# modFOC-Inputs.net
KiCad netlist of a schematic drawn in Altium Designer
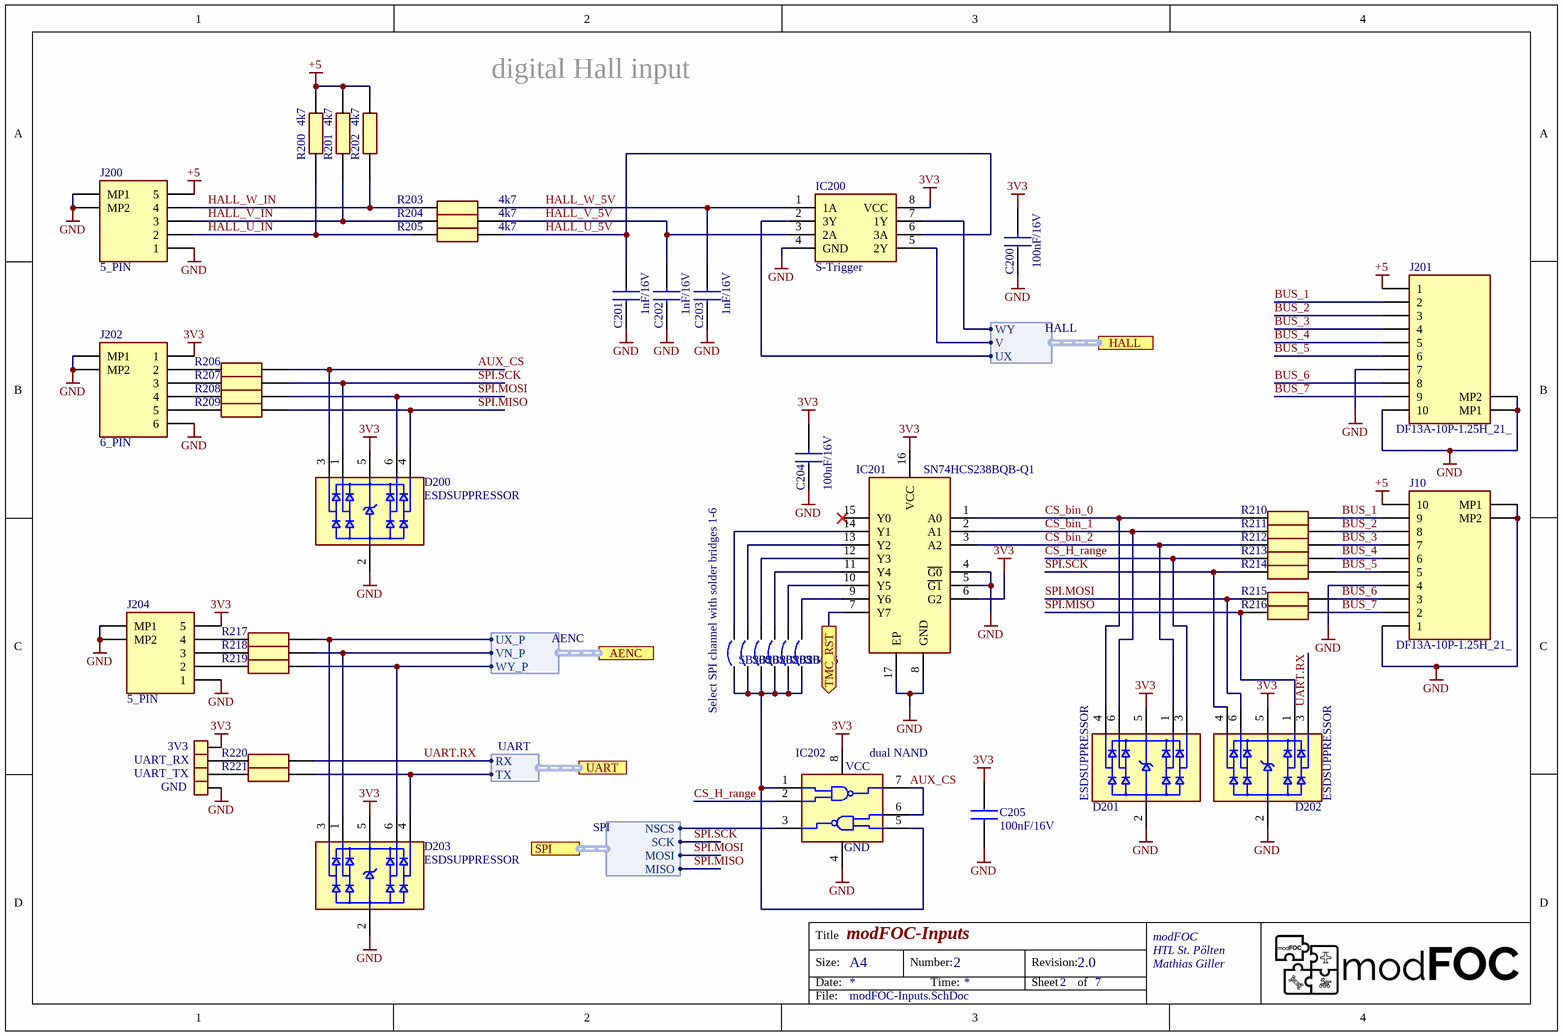
[diagram p0: modFOC-Inputs.SchDoc]

(export (version "E")
  (design (tool "Eeschema 10.0.6"))
  (components
    (comp (ref "C200")
      (value "100nF/16V")
      (footprint "CAPC1608X97N")
      (description "Capacitor")
      (libsource (lib "Schlib1") (part "C0603"))
    )
    (comp (ref "C201")
      (value "1nF/16V")
      (footprint "CAPC1608X97N")
      (description "Capacitor")
      (libsource (lib "Schlib1") (part "C0603"))
    )
    (comp (ref "C202")
      (value "1nF/16V")
      (footprint "CAPC1608X97N")
      (description "Capacitor")
      (libsource (lib "Schlib1") (part "C0603"))
    )
    (comp (ref "C203")
      (value "1nF/16V")
      (footprint "CAPC1608X97N")
      (description "Capacitor")
      (libsource (lib "Schlib1") (part "C0603"))
    )
    (comp (ref "C204")
      (value "100nF/16V")
      (footprint "CAPC1608X97N")
      (description "Capacitor")
      (libsource (lib "Schlib1") (part "C0603"))
    )
    (comp (ref "C205")
      (value "100nF/16V")
      (footprint "CAPC1608X97N")
      (description "Capacitor")
      (libsource (lib "Schlib1") (part "C0603"))
    )
    (comp (ref "D200")
      (value "ESDSUPPRESSOR")
      (footprint "SOT23-6")
      (description "TVS Diode (Uni-directional)")
      (libsource (lib "Schlib1") (part "ESDSUPPRESSOR"))
    )
    (comp (ref "D201")
      (value "ESDSUPPRESSOR")
      (footprint "SOT23-6")
      (description "TVS Diode (Uni-directional)")
      (libsource (lib "Schlib1") (part "ESDSUPPRESSOR"))
    )
    (comp (ref "D202")
      (value "ESDSUPPRESSOR")
      (footprint "SOT23-6")
      (description "TVS Diode (Uni-directional)")
      (libsource (lib "Schlib1") (part "ESDSUPPRESSOR"))
    )
    (comp (ref "D203")
      (value "ESDSUPPRESSOR")
      (footprint "SOT23-6")
      (description "TVS Diode (Uni-directional)")
      (libsource (lib "Schlib1") (part "ESDSUPPRESSOR"))
    )
    (comp (ref "IC200")
      (value "S-Trigger")
      (footprint "SOP65P400X110-8N")
      (description "3x Schmitt trigger")
      (fields
        (field (name "MANUFACTURER_PART_NUMBER") "74LVC3G17DP,125")
        (field (name "MOUSER PART NUMBER") "771-LVC3G17DP125")
      )
      (libsource (lib "Schlib1") (part "74LVC3G17DP,125"))
    )
    (comp (ref "IC201")
      (value "SN74HCS238BQB-Q1")
      (footprint "SN74HCS238BQB-Q1")
      (description "3bit bin to dec noninverting")
      (fields
        (field (name "MANUFACTURER_PART_NUMBER") "SN74HCS238QBQBRQ1")
        (field (name "MOUSER PART NUMBER") "595-N74HCS238QBQBRQ1")
      )
      (libsource (lib "Schlib1") (part "SN74HCS238BQB-Q1"))
    )
    (comp (ref "IC202")
      (value "dual NAND")
      (footprint "74AUP1G74GF115")
      (description "Dual triple input NAND")
      (fields
        (field (name "MANUFACTURER_PART_NUMBER") "74AUP2G132GF,115")
        (field (name "MOUSER PART NUMBER") "771-74AUP2G132GF115")
      )
      (libsource (lib "Schlib1") (part "74AUP2G132GF,115"))
    )
    (comp (ref "J10")
      (value "DF13A-10P-1.25H_21_")
      (footprint "DF13A10P125H21")
      (description "10Pin DF13 Connector")
      (fields
        (field (name "MANUFACTURER_PART_NUMBER") "DF13A-10P-1.25H(21)")
        (field (name "MOUSER PART NUMBER") "798-DF13A10P125H21")
      )
      (libsource (lib "") (part "DF13A-10P-1.25H_21__1"))
    )
    (comp (ref "J200")
      (value "5_PIN")
      (footprint "DF13A5P125H21")
      (description "Connector")
      (fields
        (field (name "MANUFACTURER_PART_NUMBER") "DF13A-5P-1.25H(21)")
        (field (name "MOUSER PART NUMBER") "798-DF13A5P125H21")
      )
      (libsource (lib "Schlib1") (part "DF13A-5P-1.25H_21_"))
    )
    (comp (ref "J201")
      (value "DF13A-10P-1.25H_21_")
      (footprint "DF13A10P125H21")
      (description "10Pin DF13 Connector")
      (fields
        (field (name "MANUFACTURER_PART_NUMBER") "DF13A-10P-1.25H(21)")
        (field (name "MOUSER PART NUMBER") "798-DF13A10P125H21")
      )
      (libsource (lib "Schlib1") (part "DF13A-10P-1.25H_21_"))
    )
    (comp (ref "J202")
      (value "6_PIN")
      (footprint "DF13A6P125H21")
      (description "6 Pin DF13 Connector")
      (fields
        (field (name "MANUFACTURER_PART_NUMBER") "DF13A-6P-1.25H(21)")
        (field (name "MOUSER PART NUMBER") "798-DF13A6P125H21")
      )
      (libsource (lib "Schlib1") (part "DF13A-6P-1.25H_21_"))
    )
    (comp (ref "J204")
      (value "5_PIN")
      (footprint "DF13A5P125H21")
      (description "Connector")
      (fields
        (field (name "MANUFACTURER_PART_NUMBER") "DF13A-5P-1.25H(21)")
        (field (name "MOUSER PART NUMBER") "798-DF13A5P125H21")
      )
      (libsource (lib "Schlib1") (part "DF13A-5P-1.25H_21_"))
    )
    (comp (ref "J205") (value "3V3") (footprint "Pin") (libsource (lib "Schlib1") (part "Pin")))
    (comp (ref "J206") (value "UART_RX") (footprint "Pin") (libsource (lib "Schlib1") (part "Pin")))
    (comp (ref "J207") (value "UART_TX") (footprint "Pin") (libsource (lib "Schlib1") (part "Pin")))
    (comp (ref "J208") (value "GND") (footprint "Pin") (libsource (lib "Schlib1") (part "Pin")))
    (comp (ref "R200")
      (value "4k7")
      (footprint "RESC1608X55N")
      (description "Resistor")
      (libsource (lib "Schlib1") (part "R0603"))
    )
    (comp (ref "R201")
      (value "4k7")
      (footprint "RESC1608X55N")
      (description "Resistor")
      (libsource (lib "Schlib1") (part "R0603"))
    )
    (comp (ref "R202")
      (value "4k7")
      (footprint "RESC1608X55N")
      (description "Resistor")
      (libsource (lib "Schlib1") (part "R0603"))
    )
    (comp (ref "R203")
      (value "4k7")
      (footprint "RESC1608X55N")
      (description "Resistor")
      (libsource (lib "") (part "R0603_1"))
    )
    (comp (ref "R204")
      (value "4k7")
      (footprint "RESC1608X55N")
      (description "Resistor")
      (libsource (lib "") (part "R0603_1"))
    )
    (comp (ref "R205")
      (value "4k7")
      (footprint "RESC1608X55N")
      (description "Resistor")
      (libsource (lib "") (part "R0603_1"))
    )
    (comp (ref "R206")
      (value "100R")
      (footprint "RESC1005X40N")
      (description "Resistor")
      (libsource (lib "Schlib1") (part "R0402"))
    )
    (comp (ref "R207")
      (value "100R")
      (footprint "RESC1005X40N")
      (description "Resistor")
      (libsource (lib "Schlib1") (part "R0402"))
    )
    (comp (ref "R208")
      (value "100R")
      (footprint "RESC1005X40N")
      (description "Resistor")
      (libsource (lib "Schlib1") (part "R0402"))
    )
    (comp (ref "R209")
      (value "100R")
      (footprint "RESC1005X40N")
      (description "Resistor")
      (libsource (lib "Schlib1") (part "R0402"))
    )
    (comp (ref "R210")
      (value "100R")
      (footprint "RESC1005X40N")
      (description "Resistor")
      (libsource (lib "Schlib1") (part "R0402"))
    )
    (comp (ref "R211")
      (value "100R")
      (footprint "RESC1005X40N")
      (description "Resistor")
      (libsource (lib "Schlib1") (part "R0402"))
    )
    (comp (ref "R212")
      (value "100R")
      (footprint "RESC1005X40N")
      (description "Resistor")
      (libsource (lib "Schlib1") (part "R0402"))
    )
    (comp (ref "R213")
      (value "100R")
      (footprint "RESC1005X40N")
      (description "Resistor")
      (libsource (lib "Schlib1") (part "R0402"))
    )
    (comp (ref "R214")
      (value "100R")
      (footprint "RESC1005X40N")
      (description "Resistor")
      (libsource (lib "Schlib1") (part "R0402"))
    )
    (comp (ref "R215")
      (value "100R")
      (footprint "RESC1005X40N")
      (description "Resistor")
      (libsource (lib "Schlib1") (part "R0402"))
    )
    (comp (ref "R216")
      (value "100R")
      (footprint "RESC1005X40N")
      (description "Resistor")
      (libsource (lib "Schlib1") (part "R0402"))
    )
    (comp (ref "R217")
      (value "100R")
      (footprint "RESC1005X40N")
      (description "Resistor")
      (libsource (lib "Schlib1") (part "R0402"))
    )
    (comp (ref "R218")
      (value "100R")
      (footprint "RESC1005X40N")
      (description "Resistor")
      (libsource (lib "Schlib1") (part "R0402"))
    )
    (comp (ref "R219")
      (value "100R")
      (footprint "RESC1005X40N")
      (description "Resistor")
      (libsource (lib "Schlib1") (part "R0402"))
    )
    (comp (ref "R220")
      (value "100R")
      (footprint "RESC1005X40N")
      (description "Resistor")
      (libsource (lib "Schlib1") (part "R0402"))
    )
    (comp (ref "R221")
      (value "100R")
      (footprint "RESC1005X40N")
      (description "Resistor")
      (libsource (lib "Schlib1") (part "R0402"))
    )
    (comp (ref "SB200")
      (value "Solder Bridge")
      (footprint "PcbLib1:SOLDER-BRIDGE_R0603-0R")
      (fields
        (field (name "INTERNAL_PART_NUMBER") "MCD-00071")
        (field (name "MANUFACTURER_PART_NUMBER") "RC0603JR-070RL")
        (field (name "MANUFACTURER") "YAGEO")
        (field (name "PROVIDED_BY") "SUBCO")
      )
      (libsource (lib "Schlib1") (part "Solder Bridge"))
    )
    (comp (ref "SB201")
      (value "Solder Bridge")
      (footprint "PcbLib1:SOLDER-BRIDGE_R0603-0R")
      (fields
        (field (name "INTERNAL_PART_NUMBER") "MCD-00071")
        (field (name "MANUFACTURER_PART_NUMBER") "RC0603JR-070RL")
        (field (name "MANUFACTURER") "YAGEO")
        (field (name "PROVIDED_BY") "SUBCO")
      )
      (libsource (lib "Schlib1") (part "Solder Bridge"))
    )
    (comp (ref "SB202")
      (value "Solder Bridge")
      (footprint "PcbLib1:SOLDER-BRIDGE_R0603-0R")
      (fields
        (field (name "INTERNAL_PART_NUMBER") "MCD-00071")
        (field (name "MANUFACTURER_PART_NUMBER") "RC0603JR-070RL")
        (field (name "MANUFACTURER") "YAGEO")
        (field (name "PROVIDED_BY") "SUBCO")
      )
      (libsource (lib "Schlib1") (part "Solder Bridge"))
    )
    (comp (ref "SB203")
      (value "Solder Bridge")
      (footprint "PcbLib1:SOLDER-BRIDGE_R0603-0R")
      (fields
        (field (name "INTERNAL_PART_NUMBER") "MCD-00071")
        (field (name "MANUFACTURER_PART_NUMBER") "RC0603JR-070RL")
        (field (name "MANUFACTURER") "YAGEO")
        (field (name "PROVIDED_BY") "SUBCO")
      )
      (libsource (lib "Schlib1") (part "Solder Bridge"))
    )
    (comp (ref "SB204")
      (value "Solder Bridge")
      (footprint "PcbLib1:SOLDER-BRIDGE_R0603-0R")
      (fields
        (field (name "INTERNAL_PART_NUMBER") "MCD-00071")
        (field (name "MANUFACTURER_PART_NUMBER") "RC0603JR-070RL")
        (field (name "MANUFACTURER") "YAGEO")
        (field (name "PROVIDED_BY") "SUBCO")
      )
      (libsource (lib "Schlib1") (part "Solder Bridge"))
    )
    (comp (ref "SB205")
      (value "Solder Bridge")
      (footprint "PcbLib1:SOLDER-BRIDGE_R0603-0R")
      (fields
        (field (name "INTERNAL_PART_NUMBER") "MCD-00071")
        (field (name "MANUFACTURER_PART_NUMBER") "RC0603JR-070RL")
        (field (name "MANUFACTURER") "YAGEO")
        (field (name "PROVIDED_BY") "SUBCO")
      )
      (libsource (lib "Schlib1") (part "Solder Bridge"))
    )
  )
  (nets
    (net (code "5") (name "+5") (class "Default")
      (node (ref "J10") (pin "10") (pinfunction "10_10") (pintype "passive"))
      (node (ref "J200") (pin "5") (pinfunction "5_5") (pintype "passive"))
      (node (ref "J201") (pin "1") (pinfunction "1_1") (pintype "passive"))
      (node (ref "R200") (pin "2") (pinfunction "2_2") (pintype "passive"))
      (node (ref "R201") (pin "2") (pinfunction "2_2") (pintype "passive"))
      (node (ref "R202") (pin "2") (pinfunction "2_2") (pintype "passive"))
    )
    (net (code "6") (name "/AUX_CS") (class "Default")
      (node (ref "D200") (pin "3") (pinfunction "CH1_3") (pintype "passive"))
      (node (ref "IC202") (pin "6") (pinfunction "2B_6") (pintype "passive"))
      (node (ref "IC202") (pin "7") (pinfunction "1Y_7") (pintype "passive"))
      (node (ref "R206") (pin "2") (pinfunction "2_2") (pintype "passive"))
    )
    (net (code "7") (name "/BUS_1") (class "Default")
      (node (ref "J10") (pin "9") (pinfunction "9_9") (pintype "passive"))
      (node (ref "J201") (pin "2") (pinfunction "2_2") (pintype "passive"))
      (node (ref "R210") (pin "2") (pinfunction "2_2") (pintype "passive"))
    )
    (net (code "8") (name "/BUS_2") (class "Default")
      (node (ref "J10") (pin "8") (pinfunction "8_8") (pintype "passive"))
      (node (ref "J201") (pin "3") (pinfunction "3_3") (pintype "passive"))
      (node (ref "R211") (pin "2") (pinfunction "2_2") (pintype "passive"))
    )
    (net (code "9") (name "/BUS_3") (class "Default")
      (node (ref "J10") (pin "7") (pinfunction "7_7") (pintype "passive"))
      (node (ref "J201") (pin "4") (pinfunction "4_4") (pintype "passive"))
      (node (ref "R212") (pin "2") (pinfunction "2_2") (pintype "passive"))
    )
    (net (code "10") (name "/BUS_4") (class "Default")
      (node (ref "J10") (pin "6") (pinfunction "6_6") (pintype "passive"))
      (node (ref "J201") (pin "5") (pinfunction "5_5") (pintype "passive"))
      (node (ref "R213") (pin "2") (pinfunction "2_2") (pintype "passive"))
    )
    (net (code "11") (name "/BUS_5") (class "Default")
      (node (ref "J10") (pin "5") (pinfunction "5_5") (pintype "passive"))
      (node (ref "J201") (pin "6") (pinfunction "6_6") (pintype "passive"))
      (node (ref "R214") (pin "2") (pinfunction "2_2") (pintype "passive"))
    )
    (net (code "12") (name "/BUS_6") (class "Default")
      (node (ref "J10") (pin "3") (pinfunction "3_3") (pintype "passive"))
      (node (ref "J201") (pin "8") (pinfunction "8_8") (pintype "passive"))
      (node (ref "R215") (pin "2") (pinfunction "2_2") (pintype "passive"))
    )
    (net (code "13") (name "/BUS_7") (class "Default")
      (node (ref "J10") (pin "2") (pinfunction "2_2") (pintype "passive"))
      (node (ref "J201") (pin "9") (pinfunction "9_9") (pintype "passive"))
      (node (ref "R216") (pin "2") (pinfunction "2_2") (pintype "passive"))
    )
    (net (code "14") (name "/CS_H_range") (class "Default")
      (node (ref "D201") (pin "3") (pinfunction "CH1_3") (pintype "passive"))
      (node (ref "IC202") (pin "2") (pinfunction "1B_2") (pintype "passive"))
      (node (ref "R213") (pin "1") (pinfunction "1_1") (pintype "passive"))
    )
    (net (code "15") (name "/CS_bin_0") (class "Default")
      (node (ref "D201") (pin "4") (pinfunction "CH3_4") (pintype "passive"))
      (node (ref "IC201") (pin "1") (pinfunction "A0_1") (pintype "passive"))
      (node (ref "R210") (pin "1") (pinfunction "1_1") (pintype "passive"))
    )
    (net (code "16") (name "/CS_bin_1") (class "Default")
      (node (ref "D201") (pin "6") (pinfunction "CH2_6") (pintype "passive"))
      (node (ref "IC201") (pin "2") (pinfunction "A1_2") (pintype "passive"))
      (node (ref "R211") (pin "1") (pinfunction "1_1") (pintype "passive"))
    )
    (net (code "17") (name "/CS_bin_2") (class "Default")
      (node (ref "D201") (pin "1") (pinfunction "CH4_1") (pintype "passive"))
      (node (ref "IC201") (pin "3") (pinfunction "A2_3") (pintype "passive"))
      (node (ref "R212") (pin "1") (pinfunction "1_1") (pintype "passive"))
    )
    (net (code "18") (name "/HALL_U_5V") (class "Default")
      (node (ref "C201") (pin "1") (pinfunction "1_1") (pintype "passive"))
      (node (ref "IC200") (pin "6") (pinfunction "3A_6") (pintype "passive"))
      (node (ref "R205") (pin "1") (pinfunction "1_1") (pintype "passive"))
    )
    (net (code "19") (name "/HALL_U_IN") (class "Default")
      (node (ref "J200") (pin "2") (pinfunction "2_2") (pintype "passive"))
      (node (ref "R200") (pin "1") (pinfunction "1_1") (pintype "passive"))
      (node (ref "R205") (pin "2") (pinfunction "2_2") (pintype "passive"))
    )
    (net (code "20") (name "/HALL_V_5V") (class "Default")
      (node (ref "C202") (pin "1") (pinfunction "1_1") (pintype "passive"))
      (node (ref "IC200") (pin "3") (pinfunction "2A_3") (pintype "passive"))
      (node (ref "R204") (pin "1") (pinfunction "1_1") (pintype "passive"))
    )
    (net (code "21") (name "/HALL_V_IN") (class "Default")
      (node (ref "J200") (pin "3") (pinfunction "3_3") (pintype "passive"))
      (node (ref "R201") (pin "1") (pinfunction "1_1") (pintype "passive"))
      (node (ref "R204") (pin "2") (pinfunction "2_2") (pintype "passive"))
    )
    (net (code "22") (name "/HALL_W_5V") (class "Default")
      (node (ref "C203") (pin "1") (pinfunction "1_1") (pintype "passive"))
      (node (ref "IC200") (pin "1") (pinfunction "1A_1") (pintype "passive"))
      (node (ref "R203") (pin "1") (pinfunction "1_1") (pintype "passive"))
    )
    (net (code "23") (name "/HALL_W_IN") (class "Default")
      (node (ref "J200") (pin "4") (pinfunction "4_4") (pintype "passive"))
      (node (ref "R202") (pin "1") (pinfunction "1_1") (pintype "passive"))
      (node (ref "R203") (pin "2") (pinfunction "2_2") (pintype "passive"))
    )
    (net (code "24") (name "/NSCS") (class "Default")
      (node (ref "IC202") (pin "3") (pinfunction "2Y_3") (pintype "passive"))
    )
    (net (code "25") (name "/SPI.MISO") (class "Default")
      (node (ref "D200") (pin "4") (pinfunction "CH3_4") (pintype "passive"))
      (node (ref "D202") (pin "1") (pinfunction "CH4_1") (pintype "passive"))
      (node (ref "R209") (pin "2") (pinfunction "2_2") (pintype "passive"))
      (node (ref "R216") (pin "1") (pinfunction "1_1") (pintype "passive"))
    )
    (net (code "26") (name "/SPI.MOSI") (class "Default")
      (node (ref "D200") (pin "6") (pinfunction "CH2_6") (pintype "passive"))
      (node (ref "D202") (pin "6") (pinfunction "CH2_6") (pintype "passive"))
      (node (ref "R208") (pin "2") (pinfunction "2_2") (pintype "passive"))
      (node (ref "R215") (pin "1") (pinfunction "1_1") (pintype "passive"))
    )
    (net (code "27") (name "/SPI.SCK") (class "Default")
      (node (ref "D200") (pin "1") (pinfunction "CH4_1") (pintype "passive"))
      (node (ref "D202") (pin "4") (pinfunction "CH3_4") (pintype "passive"))
      (node (ref "R207") (pin "2") (pinfunction "2_2") (pintype "passive"))
      (node (ref "R214") (pin "1") (pinfunction "1_1") (pintype "passive"))
    )
    (net (code "28") (name "/TMC_RST") (class "Default")
      (node (ref "IC201") (pin "7") (pinfunction "Y7_7") (pintype "passive"))
    )
    (net (code "29") (name "/TX") (class "Default")
      (node (ref "D203") (pin "4") (pinfunction "CH3_4") (pintype "passive"))
      (node (ref "R221") (pin "2") (pinfunction "2_2") (pintype "passive"))
    )
    (net (code "30") (name "/UART.RX") (class "Default")
      (node (ref "D202") (pin "3") (pinfunction "CH1_3") (pintype "passive"))
      (node (ref "R220") (pin "2") (pinfunction "2_2") (pintype "passive"))
    )
    (net (code "31") (name "/UX") (class "Default")
      (node (ref "IC200") (pin "2") (pinfunction "3Y_2") (pintype "passive"))
    )
    (net (code "32") (name "/UX_P") (class "Default")
      (node (ref "D203") (pin "3") (pinfunction "CH1_3") (pintype "passive"))
      (node (ref "R217") (pin "2") (pinfunction "2_2") (pintype "passive"))
    )
    (net (code "33") (name "/V") (class "Default")
      (node (ref "IC200") (pin "5") (pinfunction "2Y_5") (pintype "passive"))
    )
    (net (code "34") (name "/VN_P") (class "Default")
      (node (ref "D203") (pin "1") (pinfunction "CH4_1") (pintype "passive"))
      (node (ref "R218") (pin "2") (pinfunction "2_2") (pintype "passive"))
    )
    (net (code "35") (name "/WY") (class "Default")
      (node (ref "IC200") (pin "7") (pinfunction "1Y_7") (pintype "passive"))
    )
    (net (code "36") (name "/WY_P") (class "Default")
      (node (ref "D203") (pin "6") (pinfunction "CH2_6") (pintype "passive"))
      (node (ref "R219") (pin "2") (pinfunction "2_2") (pintype "passive"))
    )
    (net (code "41") (name "3V3") (class "Default")
      (node (ref "C200") (pin "2") (pinfunction "2_2") (pintype "passive"))
      (node (ref "C204") (pin "1") (pinfunction "1_1") (pintype "passive"))
      (node (ref "C205") (pin "1") (pinfunction "1_1") (pintype "passive"))
      (node (ref "D200") (pin "5") (pinfunction "VDD_5") (pintype "passive"))
      (node (ref "D201") (pin "5") (pinfunction "VDD_5") (pintype "passive"))
      (node (ref "D202") (pin "5") (pinfunction "VDD_5") (pintype "passive"))
      (node (ref "D203") (pin "5") (pinfunction "VDD_5") (pintype "passive"))
      (node (ref "IC200") (pin "8") (pinfunction "VCC_8") (pintype "passive"))
      (node (ref "IC201") (pin "16") (pinfunction "VCC_16") (pintype "passive"))
      (node (ref "IC201") (pin "6") (pinfunction "G2_6") (pintype "passive"))
      (node (ref "IC202") (pin "8") (pintype "passive"))
      (node (ref "J202") (pin "1") (pinfunction "1_1") (pintype "passive"))
      (node (ref "J204") (pin "5") (pinfunction "5_5") (pintype "passive"))
      (node (ref "J205") (pin "1") (pinfunction "1_1") (pintype "passive"))
    )
    (net (code "42") (name "GND") (class "Default")
      (node (ref "C200") (pin "1") (pinfunction "1_1") (pintype "passive"))
      (node (ref "C201") (pin "2") (pinfunction "2_2") (pintype "passive"))
      (node (ref "C202") (pin "2") (pinfunction "2_2") (pintype "passive"))
      (node (ref "C203") (pin "2") (pinfunction "2_2") (pintype "passive"))
      (node (ref "C204") (pin "2") (pinfunction "2_2") (pintype "passive"))
      (node (ref "C205") (pin "2") (pinfunction "2_2") (pintype "passive"))
      (node (ref "D200") (pin "2") (pinfunction "GND_2") (pintype "passive"))
      (node (ref "D201") (pin "2") (pinfunction "GND_2") (pintype "passive"))
      (node (ref "D202") (pin "2") (pinfunction "GND_2") (pintype "passive"))
      (node (ref "D203") (pin "2") (pinfunction "GND_2") (pintype "passive"))
      (node (ref "IC200") (pin "4") (pinfunction "GND_4") (pintype "passive"))
      (node (ref "IC201") (pin "17") (pinfunction "EP_17") (pintype "passive"))
      (node (ref "IC201") (pin "4") (pinfunction "~{G0}_4") (pintype "passive"))
      (node (ref "IC201") (pin "5") (pinfunction "~{G1}_5") (pintype "passive"))
      (node (ref "IC201") (pin "8") (pinfunction "GND_8") (pintype "passive"))
      (node (ref "IC202") (pin "4") (pintype "passive"))
      (node (ref "J10") (pin "1") (pinfunction "1_1") (pintype "passive"))
      (node (ref "J10") (pin "4") (pinfunction "4_4") (pintype "passive"))
      (node (ref "J10") (pin "MP1") (pinfunction "MP1_MP1") (pintype "passive"))
      (node (ref "J10") (pin "MP2") (pinfunction "MP2_MP2") (pintype "passive"))
      (node (ref "J200") (pin "1") (pinfunction "1_1") (pintype "passive"))
      (node (ref "J200") (pin "MP1") (pinfunction "MP1_MP1") (pintype "passive"))
      (node (ref "J200") (pin "MP2") (pinfunction "MP2_MP2") (pintype "passive"))
      (node (ref "J201") (pin "10") (pinfunction "10_10") (pintype "passive"))
      (node (ref "J201") (pin "7") (pinfunction "7_7") (pintype "passive"))
      (node (ref "J201") (pin "MP1") (pinfunction "MP1_MP1") (pintype "passive"))
      (node (ref "J201") (pin "MP2") (pinfunction "MP2_MP2") (pintype "passive"))
      (node (ref "J202") (pin "6") (pinfunction "6_6") (pintype "passive"))
      (node (ref "J202") (pin "MP1") (pinfunction "MP1_MP1") (pintype "passive"))
      (node (ref "J202") (pin "MP2") (pinfunction "MP2_MP2") (pintype "passive"))
      (node (ref "J204") (pin "1") (pinfunction "1_1") (pintype "passive"))
      (node (ref "J204") (pin "MP1") (pinfunction "MP1_MP1") (pintype "passive"))
      (node (ref "J204") (pin "MP2") (pinfunction "MP2_MP2") (pintype "passive"))
      (node (ref "J208") (pin "1") (pinfunction "1_1") (pintype "passive"))
    )
    (net (code "43") (name "Net-(IC201-Y1)") (class "Default")
      (node (ref "IC201") (pin "14") (pinfunction "Y1_14") (pintype "passive"))
      (node (ref "SB200") (pin "2") (pinfunction "2_2") (pintype "passive"))
    )
    (net (code "44") (name "Net-(IC201-Y2)") (class "Default")
      (node (ref "IC201") (pin "13") (pinfunction "Y2_13") (pintype "passive"))
      (node (ref "SB201") (pin "2") (pinfunction "2_2") (pintype "passive"))
    )
    (net (code "45") (name "Net-(IC201-Y3)") (class "Default")
      (node (ref "IC201") (pin "12") (pinfunction "Y3_12") (pintype "passive"))
      (node (ref "SB202") (pin "2") (pinfunction "2_2") (pintype "passive"))
    )
    (net (code "46") (name "Net-(IC201-Y4)") (class "Default")
      (node (ref "IC201") (pin "11") (pinfunction "Y4_11") (pintype "passive"))
      (node (ref "SB203") (pin "2") (pinfunction "2_2") (pintype "passive"))
    )
    (net (code "47") (name "Net-(IC201-Y5)") (class "Default")
      (node (ref "IC201") (pin "10") (pinfunction "Y5_10") (pintype "passive"))
      (node (ref "SB204") (pin "2") (pinfunction "2_2") (pintype "passive"))
    )
    (net (code "48") (name "Net-(IC201-Y6)") (class "Default")
      (node (ref "IC201") (pin "9") (pinfunction "Y6_9") (pintype "passive"))
      (node (ref "SB205") (pin "2") (pinfunction "2_2") (pintype "passive"))
    )
    (net (code "49") (name "Net-(IC202-1A)") (class "Default")
      (node (ref "IC202") (pin "1") (pinfunction "1A_1") (pintype "passive"))
      (node (ref "IC202") (pin "5") (pinfunction "2A_5") (pintype "passive"))
      (node (ref "SB200") (pin "1") (pinfunction "1_1") (pintype "passive"))
      (node (ref "SB201") (pin "1") (pinfunction "1_1") (pintype "passive"))
      (node (ref "SB202") (pin "1") (pinfunction "1_1") (pintype "passive"))
      (node (ref "SB203") (pin "1") (pinfunction "1_1") (pintype "passive"))
      (node (ref "SB204") (pin "1") (pinfunction "1_1") (pintype "passive"))
      (node (ref "SB205") (pin "1") (pinfunction "1_1") (pintype "passive"))
    )
    (net (code "50") (name "Net-(J202-Pad2)") (class "Default")
      (node (ref "J202") (pin "2") (pinfunction "2_2") (pintype "passive"))
      (node (ref "R206") (pin "1") (pinfunction "1_1") (pintype "passive"))
    )
    (net (code "51") (name "Net-(J202-Pad3)") (class "Default")
      (node (ref "J202") (pin "3") (pinfunction "3_3") (pintype "passive"))
      (node (ref "R207") (pin "1") (pinfunction "1_1") (pintype "passive"))
    )
    (net (code "52") (name "Net-(J202-Pad4)") (class "Default")
      (node (ref "J202") (pin "4") (pinfunction "4_4") (pintype "passive"))
      (node (ref "R208") (pin "1") (pinfunction "1_1") (pintype "passive"))
    )
    (net (code "53") (name "Net-(J202-Pad5)") (class "Default")
      (node (ref "J202") (pin "5") (pinfunction "5_5") (pintype "passive"))
      (node (ref "R209") (pin "1") (pinfunction "1_1") (pintype "passive"))
    )
    (net (code "54") (name "Net-(J204-Pad2)") (class "Default")
      (node (ref "J204") (pin "2") (pinfunction "2_2") (pintype "passive"))
      (node (ref "R219") (pin "1") (pinfunction "1_1") (pintype "passive"))
    )
    (net (code "55") (name "Net-(J204-Pad3)") (class "Default")
      (node (ref "J204") (pin "3") (pinfunction "3_3") (pintype "passive"))
      (node (ref "R218") (pin "1") (pinfunction "1_1") (pintype "passive"))
    )
    (net (code "56") (name "Net-(J204-Pad4)") (class "Default")
      (node (ref "J204") (pin "4") (pinfunction "4_4") (pintype "passive"))
      (node (ref "R217") (pin "1") (pinfunction "1_1") (pintype "passive"))
    )
    (net (code "57") (name "Net-(J206-Pad1)") (class "Default")
      (node (ref "J206") (pin "1") (pinfunction "1_1") (pintype "passive"))
      (node (ref "R220") (pin "1") (pinfunction "1_1") (pintype "passive"))
    )
    (net (code "58") (name "Net-(J207-Pad1)") (class "Default")
      (node (ref "J207") (pin "1") (pinfunction "1_1") (pintype "passive"))
      (node (ref "R221") (pin "1") (pinfunction "1_1") (pintype "passive"))
    )
    (net (code "59") (name "unconnected-(IC201-Y0-Pad15)") (class "Default")
      (node (ref "IC201") (pin "15") (pinfunction "Y0_15") (pintype "passive+no_connect"))
    )
  )
)
